# mix.net
KiCad netlist of a schematic drawn in Altium Designer
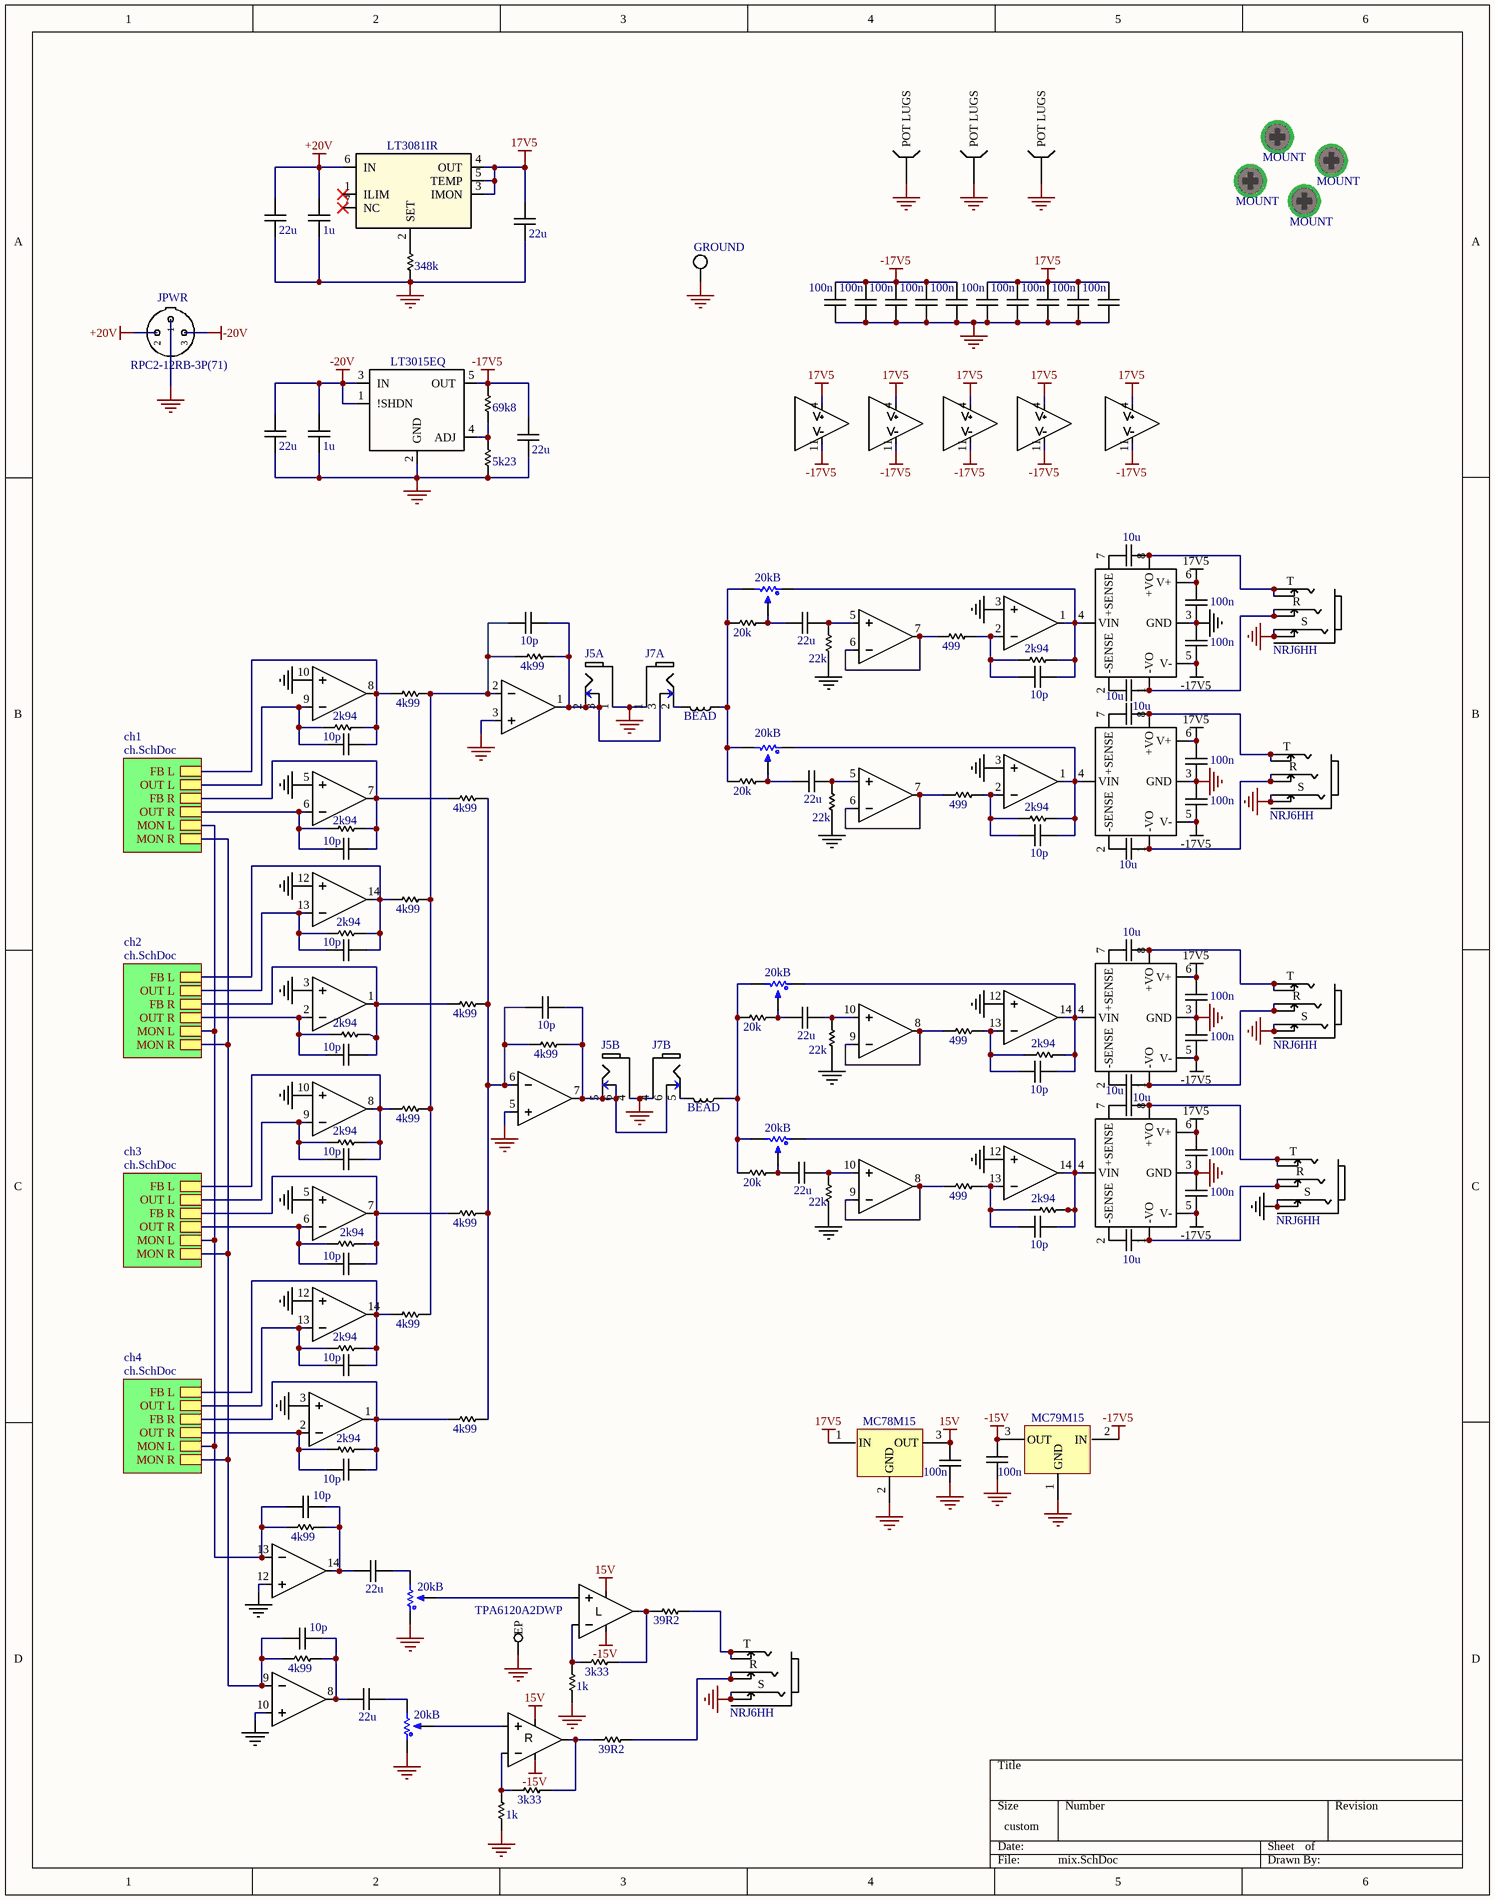
[diagram p0: mix.SchDoc]

(export (version "E")
  (design (tool "Eeschema 10.0.6"))
  (components
    (comp (ref "C5")
      (value "100n")
      (footprint "0805")
      (fields (field (name "PARTNUMBER") "C0805C104K1RAC7800"))
      (libsource (lib "mix") (part "CAP"))
    )
    (comp (ref "C7")
      (value "100n")
      (footprint "0805")
      (fields (field (name "PARTNUMBER") "C0805C104K1RAC7800"))
      (libsource (lib "mix") (part "CAP"))
    )
    (comp (ref "C15")
      (value "100n")
      (footprint "0805")
      (fields (field (name "PARTNUMBER") "C0805C104K1RAC7800"))
      (libsource (lib "mix") (part "CAP"))
    )
    (comp (ref "C17")
      (value "100n")
      (footprint "0805")
      (fields (field (name "PARTNUMBER") "C0805C104K1RAC7800"))
      (libsource (lib "mix") (part "CAP"))
    )
    (comp (ref "C23")
      (value "10p")
      (footprint "0805")
      (fields (field (name "PARTNUMBER") "CC0805JRNPO9BN100"))
      (libsource (lib "mix") (part "CAP"))
    )
    (comp (ref "C24")
      (value "100n")
      (footprint "0805")
      (fields (field (name "PARTNUMBER") "C0805C104K1RAC7800"))
      (libsource (lib "mix") (part "CAP"))
    )
    (comp (ref "C26")
      (value "100n")
      (footprint "0805")
      (fields (field (name "PARTNUMBER") "C0805C104K1RAC7800"))
      (libsource (lib "mix") (part "CAP"))
    )
    (comp (ref "C31")
      (value "100n")
      (footprint "0805")
      (fields (field (name "PARTNUMBER") "C0805C104K1RAC7800"))
      (libsource (lib "mix") (part "CAP"))
    )
    (comp (ref "C33")
      (value "100n")
      (footprint "0805")
      (fields (field (name "PARTNUMBER") "C0805C104K1RAC7800"))
      (libsource (lib "mix") (part "CAP"))
    )
    (comp (ref "C36")
      (value "22u")
      (footprint "0805")
      (fields (field (name "PARTNUMBER") "GRT21BR61E226ME13L"))
      (libsource (lib "mix") (part "CAP"))
    )
    (comp (ref "C37")
      (value "10p")
      (footprint "0805")
      (fields (field (name "PARTNUMBER") "CC0805JRNPO9BN100"))
      (libsource (lib "mix") (part "CAP"))
    )
    (comp (ref "C38")
      (value "100n")
      (footprint "0805")
      (fields (field (name "PARTNUMBER") "C0805C104K1RAC7800"))
      (libsource (lib "mix") (part "CAP"))
    )
    (comp (ref "C39")
      (value "22u")
      (footprint "0805")
      (fields (field (name "PARTNUMBER") "GRT21BR61E226ME13L"))
      (libsource (lib "mix") (part "CAP"))
    )
    (comp (ref "C40")
      (value "100n")
      (footprint "0805")
      (fields (field (name "PARTNUMBER") "C0805C104K1RAC7800"))
      (libsource (lib "mix") (part "CAP"))
    )
    (comp (ref "C41")
      (value "10p")
      (footprint "0805")
      (fields (field (name "PARTNUMBER") "CC0805JRNPO9BN100"))
      (libsource (lib "mix") (part "CAP"))
    )
    (comp (ref "C43")
      (value "10p")
      (footprint "0805")
      (fields (field (name "PARTNUMBER") "CC0805JRNPO9BN100"))
      (libsource (lib "mix") (part "CAP"))
    )
    (comp (ref "C45")
      (value "10p")
      (footprint "0805")
      (fields (field (name "PARTNUMBER") "CC0805JRNPO9BN100"))
      (libsource (lib "mix") (part "CAP"))
    )
    (comp (ref "C46")
      (value "100n")
      (footprint "0805")
      (fields (field (name "PARTNUMBER") "C0805C104K1RAC7800"))
      (libsource (lib "mix") (part "CAP"))
    )
    (comp (ref "C47")
      (value "10p")
      (footprint "0805")
      (fields (field (name "PARTNUMBER") "CC0805JRNPO9BN100"))
      (libsource (lib "mix") (part "CAP"))
    )
    (comp (ref "C48")
      (value "22u")
      (footprint "0805")
      (fields (field (name "PARTNUMBER") "GRT21BR61E226ME13L"))
      (libsource (lib "mix") (part "CAP"))
    )
    (comp (ref "C49")
      (value "100n")
      (footprint "0805")
      (fields (field (name "PARTNUMBER") "C0805C104K1RAC7800"))
      (libsource (lib "mix") (part "CAP"))
    )
    (comp (ref "C50")
      (value "10p")
      (footprint "0805")
      (fields (field (name "PARTNUMBER") "CC0805JRNPO9BN100"))
      (libsource (lib "mix") (part "CAP"))
    )
    (comp (ref "C52")
      (value "22u")
      (footprint "0805")
      (fields (field (name "PARTNUMBER") "GRT21BR61E226ME13L"))
      (libsource (lib "mix") (part "CAP"))
    )
    (comp (ref "C54")
      (value "10p")
      (footprint "0805")
      (fields (field (name "PARTNUMBER") "CC0805JRNPO9BN100"))
      (libsource (lib "mix") (part "CAP"))
    )
    (comp (ref "C55")
      (value "22u")
      (footprint "0805")
      (fields (field (name "PARTNUMBER") "GRT21BR61E226ME13L"))
      (libsource (lib "mix") (part "CAP"))
    )
    (comp (ref "C56")
      (value "10p")
      (footprint "0805")
      (fields (field (name "PARTNUMBER") "CC0805JRNPO9BN100"))
      (libsource (lib "mix") (part "CAP"))
    )
    (comp (ref "C57")
      (value "22u")
      (footprint "0805")
      (fields (field (name "PARTNUMBER") "GRT21BR61E226ME13L"))
      (libsource (lib "mix") (part "CAP"))
    )
    (comp (ref "C58")
      (value "10p")
      (footprint "0805")
      (fields (field (name "PARTNUMBER") "CC0805JRNPO9BN100"))
      (libsource (lib "mix") (part "CAP"))
    )
    (comp (ref "C59")
      (value "10p")
      (footprint "0805")
      (fields (field (name "PARTNUMBER") "CC0805JRNPO9BN100"))
      (libsource (lib "mix") (part "CAP"))
    )
    (comp (ref "C60")
      (value "10p")
      (footprint "0805")
      (fields (field (name "PARTNUMBER") "CC0805JRNPO9BN100"))
      (libsource (lib "mix") (part "CAP"))
    )
    (comp (ref "C61")
      (value "10p")
      (footprint "0805")
      (fields (field (name "PARTNUMBER") "CC0805JRNPO9BN100"))
      (libsource (lib "mix") (part "CAP"))
    )
    (comp (ref "C62")
      (value "10p")
      (footprint "0805")
      (fields (field (name "PARTNUMBER") "CC0805JRNPO9BN100"))
      (libsource (lib "mix") (part "CAP"))
    )
    (comp (ref "C63")
      (value "10p")
      (footprint "0805")
      (fields (field (name "PARTNUMBER") "CC0805JRNPO9BN100"))
      (libsource (lib "mix") (part "CAP"))
    )
    (comp (ref "C64")
      (value "10p")
      (footprint "0805")
      (fields (field (name "PARTNUMBER") "CC0805JRNPO9BN100"))
      (libsource (lib "mix") (part "CAP"))
    )
    (comp (ref "C983")
      (value "22u")
      (footprint "0805")
      (fields (field (name "PARTNUMBER") "GRT21BR61E226ME13L"))
      (libsource (lib "mix") (part "CAP"))
    )
    (comp (ref "C984")
      (value "1u")
      (footprint "0805")
      (fields (field (name "PARTNUMBER") "CL21B105KBFNNNF"))
      (libsource (lib "mix") (part "CAP"))
    )
    (comp (ref "C985")
      (value "22u")
      (footprint "0805")
      (fields (field (name "PARTNUMBER") "GRT21BR61E226ME13L"))
      (libsource (lib "mix") (part "CAP"))
    )
    (comp (ref "C988")
      (value "22u")
      (footprint "0805")
      (fields (field (name "PARTNUMBER") "GRT21BR61E226ME13L"))
      (libsource (lib "mix") (part "CAP"))
    )
    (comp (ref "C989")
      (value "1u")
      (footprint "0805")
      (fields (field (name "PARTNUMBER") "CL21B105KBFNNNF"))
      (libsource (lib "mix") (part "CAP"))
    )
    (comp (ref "C990")
      (value "22u")
      (footprint "0805")
      (fields (field (name "PARTNUMBER") "GRT21BR61E226ME13L"))
      (libsource (lib "mix") (part "CAP"))
    )
    (comp (ref "C1002")
      (value "100n")
      (footprint "0805")
      (fields (field (name "PARTNUMBER") "C0805C104K1RAC7800"))
      (libsource (lib "mix") (part "CAP"))
    )
    (comp (ref "C1003")
      (value "100n")
      (footprint "0805")
      (fields (field (name "PARTNUMBER") "C0805C104K1RAC7800"))
      (libsource (lib "mix") (part "CAP"))
    )
    (comp (ref "C1004")
      (value "100n")
      (footprint "0805")
      (fields (field (name "PARTNUMBER") "C0805C104K1RAC7800"))
      (libsource (lib "mix") (part "CAP"))
    )
    (comp (ref "C1005")
      (value "100n")
      (footprint "0805")
      (fields (field (name "PARTNUMBER") "C0805C104K1RAC7800"))
      (libsource (lib "mix") (part "CAP"))
    )
    (comp (ref "C1006")
      (value "100n")
      (footprint "0805")
      (fields (field (name "PARTNUMBER") "C0805C104K1RAC7800"))
      (libsource (lib "mix") (part "CAP"))
    )
    (comp (ref "C1007")
      (value "100n")
      (footprint "0805")
      (fields (field (name "PARTNUMBER") "C0805C104K1RAC7800"))
      (libsource (lib "mix") (part "CAP"))
    )
    (comp (ref "C1008")
      (value "100n")
      (footprint "0805")
      (fields (field (name "PARTNUMBER") "C0805C104K1RAC7800"))
      (libsource (lib "mix") (part "CAP"))
    )
    (comp (ref "C1010")
      (value "100n")
      (footprint "0805")
      (fields (field (name "PARTNUMBER") "C0805C104K1RAC7800"))
      (libsource (lib "mix") (part "CAP"))
    )
    (comp (ref "C2001")
      (value "10u")
      (footprint "0805")
      (fields (field (name "PARTNUMBER") "NMC0805X5R106K25TRPLP2KF"))
      (libsource (lib "mix") (part "CAP"))
    )
    (comp (ref "C2002")
      (value "10u")
      (footprint "0805")
      (fields (field (name "PARTNUMBER") "NMC0805X5R106K25TRPLP2KF"))
      (libsource (lib "mix") (part "CAP"))
    )
    (comp (ref "C2003")
      (value "10u")
      (footprint "0805")
      (fields (field (name "PARTNUMBER") "NMC0805X5R106K25TRPLP2KF"))
      (libsource (lib "mix") (part "CAP"))
    )
    (comp (ref "C2004")
      (value "10u")
      (footprint "0805")
      (fields (field (name "PARTNUMBER") "NMC0805X5R106K25TRPLP2KF"))
      (libsource (lib "mix") (part "CAP"))
    )
    (comp (ref "C2005")
      (value "10u")
      (footprint "0805")
      (fields (field (name "PARTNUMBER") "NMC0805X5R106K25TRPLP2KF"))
      (libsource (lib "mix") (part "CAP"))
    )
    (comp (ref "C2006")
      (value "10u")
      (footprint "0805")
      (fields (field (name "PARTNUMBER") "NMC0805X5R106K25TRPLP2KF"))
      (libsource (lib "mix") (part "CAP"))
    )
    (comp (ref "C2007")
      (value "10u")
      (footprint "0805")
      (fields (field (name "PARTNUMBER") "NMC0805X5R106K25TRPLP2KF"))
      (libsource (lib "mix") (part "CAP"))
    )
    (comp (ref "C2008")
      (value "10u")
      (footprint "0805")
      (fields (field (name "PARTNUMBER") "NMC0805X5R106K25TRPLP2KF"))
      (libsource (lib "mix") (part "CAP"))
    )
    (comp (ref "GROUND") (value "PHONO") (footprint "PAD") (libsource (lib "mix") (part "PAD")))
    (comp (ref "J1")
      (value "NRJ6HH")
      (footprint "NRJ6HH")
      (fields (field (name "PARTNUMBER") "NRJ6HH-AU"))
      (libsource (lib "mix") (part "NRJ6HH"))
    )
    (comp (ref "J2")
      (value "NRJ6HH")
      (footprint "NRJ6HH")
      (fields (field (name "PARTNUMBER") "NRJ6HH-AU"))
      (libsource (lib "mix") (part "NRJ6HH"))
    )
    (comp (ref "J3")
      (value "NRJ6HH")
      (footprint "NRJ6HH")
      (fields (field (name "PARTNUMBER") "NRJ6HH-AU"))
      (libsource (lib "mix") (part "NRJ6HH"))
    )
    (comp (ref "J4")
      (value "NRJ6HH")
      (footprint "NRJ6HH")
      (fields (field (name "PARTNUMBER") "NRJ6HH-AU"))
      (libsource (lib "mix") (part "NRJ6HH"))
    )
    (comp (ref "J5")
      (value "PJRAN2X1U01AUX")
      (footprint "PJRAN2X1U01AUX")
      (libsource (lib "mix") (part "PJRAN2X1U01AUX"))
    )
    (comp (ref "J6")
      (value "NRJ6HH")
      (footprint "NRJ6HH")
      (fields (field (name "PARTNUMBER") "NRJ6HH-AU"))
      (libsource (lib "mix") (part "NRJ6HH"))
    )
    (comp (ref "J7")
      (value "PJRAN2X1U01AUX")
      (footprint "PJRAN2X1U01AUX")
      (libsource (lib "mix") (part "PJRAN2X1U01AUX"))
    )
    (comp (ref "JPWR")
      (value "RPC2-12RB-3P(71)")
      (footprint "RPC2-12RB-3P(71)")
      (libsource (lib "mix") (part "RPC2-12RB-3P(71)"))
    )
    (comp (ref "L3")
      (value "BEAD")
      (footprint "0805")
      (fields (field (name "PARTNUMBER") "BLM21PG121SH1D"))
      (libsource (lib "mix") (part "BLM21PG121SH1D"))
    )
    (comp (ref "L4")
      (value "BEAD")
      (footprint "0805")
      (fields (field (name "PARTNUMBER") "BLM21PG121SH1D"))
      (libsource (lib "mix") (part "BLM21PG121SH1D"))
    )
    (comp (ref "MH1") (value "MOUNT") (footprint "MOUNT") (libsource (lib "mix") (part "MOUNT")))
    (comp (ref "MH2") (value "MOUNT") (footprint "MOUNT") (libsource (lib "mix") (part "MOUNT")))
    (comp (ref "MH3") (value "MOUNT") (footprint "MOUNT") (libsource (lib "mix") (part "MOUNT")))
    (comp (ref "MH4") (value "MOUNT") (footprint "MOUNT") (libsource (lib "mix") (part "MOUNT")))
    (comp (ref "R5")
      (value "20kB")
      (footprint "P0925N-FC15AR10K")
      (description "P0925N-FC15BR20K")
      (libsource (lib "") (part "P0925N-FC15BR20K_2"))
    )
    (comp (ref "R6")
      (value "20kB")
      (footprint "P0925N-FC15AR10K")
      (description "P0925N-FC15BR20K")
      (libsource (lib "") (part "P0925N-FC15BR20K_2"))
    )
    (comp (ref "R7")
      (value "20kB")
      (footprint "P0925N-FC15AR10K")
      (description "P0925N-FC15BR20K")
      (libsource (lib "") (part "P0925N-FC15BR20K_2"))
    )
    (comp (ref "R13")
      (value "4k99")
      (footprint "0805")
      (fields (field (name "PARTNUMBER") "ERJ-6ENF4991V"))
      (libsource (lib "mix") (part "RES"))
    )
    (comp (ref "R26")
      (value "3k33")
      (footprint "0805")
      (fields (field (name "PARTNUMBER") "ERJ-6ENF1002V"))
      (libsource (lib "mix") (part "RES"))
    )
    (comp (ref "R27")
      (value "3k33")
      (footprint "0805")
      (fields (field (name "PARTNUMBER") "ERJ-6ENF1002V"))
      (libsource (lib "mix") (part "RES"))
    )
    (comp (ref "R29")
      (value "1k")
      (footprint "0805")
      (fields (field (name "PARTNUMBER") "ERJ-6ENF1001V"))
      (libsource (lib "mix") (part "RES"))
    )
    (comp (ref "R30")
      (value "39R2")
      (footprint "0805")
      (fields (field (name "PARTNUMBER") "ERJ-6ENF39R2V"))
      (libsource (lib "mix") (part "RES"))
    )
    (comp (ref "R31")
      (value "39R2")
      (footprint "0805")
      (fields (field (name "PARTNUMBER") "ERJ-6ENF39R2V"))
      (libsource (lib "mix") (part "RES"))
    )
    (comp (ref "R32")
      (value "1k")
      (footprint "0805")
      (fields (field (name "PARTNUMBER") "ERJ-6ENF1001V"))
      (libsource (lib "mix") (part "RES"))
    )
    (comp (ref "R47")
      (value "499")
      (footprint "0805")
      (fields (field (name "PARTNUMBER") "ERJ-6ENF4990V"))
      (libsource (lib "mix") (part "RES"))
    )
    (comp (ref "R49")
      (value "22k")
      (footprint "0805")
      (fields (field (name "PARTNUMBER") "ERJ-6ENF2202V"))
      (libsource (lib "mix") (part "RES"))
    )
    (comp (ref "R50")
      (value "2k94")
      (footprint "0805")
      (fields (field (name "PARTNUMBER") "ERJ-6ENF2941V"))
      (libsource (lib "mix") (part "RES"))
    )
    (comp (ref "R51")
      (value "4k99")
      (footprint "0805")
      (fields (field (name "PARTNUMBER") "ERJ-6ENF4991V"))
      (libsource (lib "mix") (part "RES"))
    )
    (comp (ref "R71")
      (value "20k")
      (footprint "0805")
      (fields (field (name "PARTNUMBER") "ERJ-6ENF2002V"))
      (libsource (lib "mix") (part "RES"))
    )
    (comp (ref "R75")
      (value "20k")
      (footprint "0805")
      (fields (field (name "PARTNUMBER") "ERJ-6ENF2002V"))
      (libsource (lib "mix") (part "RES"))
    )
    (comp (ref "R76")
      (value "499")
      (footprint "0805")
      (fields (field (name "PARTNUMBER") "ERJ-6ENF4990V"))
      (libsource (lib "mix") (part "RES"))
    )
    (comp (ref "R77")
      (value "2k94")
      (footprint "0805")
      (fields (field (name "PARTNUMBER") "ERJ-6ENF2941V"))
      (libsource (lib "mix") (part "RES"))
    )
    (comp (ref "R78")
      (value "22k")
      (footprint "0805")
      (fields (field (name "PARTNUMBER") "ERJ-6ENF2202V"))
      (libsource (lib "mix") (part "RES"))
    )
    (comp (ref "R79")
      (value "2k94")
      (footprint "0805")
      (fields (field (name "PARTNUMBER") "ERJ-6ENF2941V"))
      (libsource (lib "mix") (part "RES"))
    )
    (comp (ref "R80")
      (value "4k99")
      (footprint "0805")
      (fields (field (name "PARTNUMBER") "ERJ-6ENF4991V"))
      (libsource (lib "mix") (part "RES"))
    )
    (comp (ref "R81")
      (value "2k94")
      (footprint "0805")
      (fields (field (name "PARTNUMBER") "ERJ-6ENF2941V"))
      (libsource (lib "mix") (part "RES"))
    )
    (comp (ref "R82")
      (value "4k99")
      (footprint "0805")
      (fields (field (name "PARTNUMBER") "ERJ-6ENF4991V"))
      (libsource (lib "mix") (part "RES"))
    )
    (comp (ref "R83")
      (value "2k94")
      (footprint "0805")
      (fields (field (name "PARTNUMBER") "ERJ-6ENF2941V"))
      (libsource (lib "mix") (part "RES"))
    )
    (comp (ref "R84")
      (value "499")
      (footprint "0805")
      (fields (field (name "PARTNUMBER") "ERJ-6ENF4990V"))
      (libsource (lib "mix") (part "RES"))
    )
    (comp (ref "R85")
      (value "4k99")
      (footprint "0805")
      (fields (field (name "PARTNUMBER") "ERJ-6ENF4991V"))
      (libsource (lib "mix") (part "RES"))
    )
    (comp (ref "R86")
      (value "22k")
      (footprint "0805")
      (fields (field (name "PARTNUMBER") "ERJ-6ENF2202V"))
      (libsource (lib "mix") (part "RES"))
    )
    (comp (ref "R87")
      (value "2k94")
      (footprint "0805")
      (fields (field (name "PARTNUMBER") "ERJ-6ENF2941V"))
      (libsource (lib "mix") (part "RES"))
    )
    (comp (ref "R88")
      (value "4k99")
      (footprint "0805")
      (fields (field (name "PARTNUMBER") "ERJ-6ENF4991V"))
      (libsource (lib "mix") (part "RES"))
    )
    (comp (ref "R89")
      (value "2k94")
      (footprint "0805")
      (fields (field (name "PARTNUMBER") "ERJ-6ENF2941V"))
      (libsource (lib "mix") (part "RES"))
    )
    (comp (ref "R90")
      (value "499")
      (footprint "0805")
      (fields (field (name "PARTNUMBER") "ERJ-6ENF4990V"))
      (libsource (lib "mix") (part "RES"))
    )
    (comp (ref "R91")
      (value "22k")
      (footprint "0805")
      (fields (field (name "PARTNUMBER") "ERJ-6ENF2202V"))
      (libsource (lib "mix") (part "RES"))
    )
    (comp (ref "R92")
      (value "4k99")
      (footprint "0805")
      (fields (field (name "PARTNUMBER") "ERJ-6ENF4991V"))
      (libsource (lib "mix") (part "RES"))
    )
    (comp (ref "R93")
      (value "2k94")
      (footprint "0805")
      (fields (field (name "PARTNUMBER") "ERJ-6ENF2941V"))
      (libsource (lib "mix") (part "RES"))
    )
    (comp (ref "R94")
      (value "2k94")
      (footprint "0805")
      (fields (field (name "PARTNUMBER") "ERJ-6ENF2941V"))
      (libsource (lib "mix") (part "RES"))
    )
    (comp (ref "R95")
      (value "4k99")
      (footprint "0805")
      (fields (field (name "PARTNUMBER") "ERJ-6ENF4991V"))
      (libsource (lib "mix") (part "RES"))
    )
    (comp (ref "R96")
      (value "2k94")
      (footprint "0805")
      (fields (field (name "PARTNUMBER") "ERJ-6ENF2941V"))
      (libsource (lib "mix") (part "RES"))
    )
    (comp (ref "R97")
      (value "4k99")
      (footprint "0805")
      (fields (field (name "PARTNUMBER") "ERJ-6ENF4991V"))
      (libsource (lib "mix") (part "RES"))
    )
    (comp (ref "R98")
      (value "2k94")
      (footprint "0805")
      (fields (field (name "PARTNUMBER") "ERJ-6ENF2941V"))
      (libsource (lib "mix") (part "RES"))
    )
    (comp (ref "R99")
      (value "4k99")
      (footprint "0805")
      (fields (field (name "PARTNUMBER") "ERJ-6ENF4991V"))
      (libsource (lib "mix") (part "RES"))
    )
    (comp (ref "R100")
      (value "2k94")
      (footprint "0805")
      (fields (field (name "PARTNUMBER") "ERJ-6ENF2941V"))
      (libsource (lib "mix") (part "RES"))
    )
    (comp (ref "R101")
      (value "348k")
      (footprint "0805")
      (fields (field (name "PARTNUMBER") "ERJ-PB6B3483V"))
      (libsource (lib "mix") (part "RES"))
    )
    (comp (ref "R102")
      (value "5k23")
      (footprint "0805")
      (fields (field (name "PARTNUMBER") "ERJ-PB6B5231V"))
      (libsource (lib "mix") (part "RES"))
    )
    (comp (ref "R103")
      (value "69k8")
      (footprint "0805")
      (fields (field (name "PARTNUMBER") "ERJ-PB6B6982V"))
      (libsource (lib "mix") (part "RES"))
    )
    (comp (ref "R104")
      (value "20k")
      (footprint "0805")
      (fields (field (name "PARTNUMBER") "ERJ-6ENF2002V"))
      (libsource (lib "mix") (part "RES"))
    )
    (comp (ref "R105")
      (value "20k")
      (footprint "0805")
      (fields (field (name "PARTNUMBER") "ERJ-6ENF2002V"))
      (libsource (lib "mix") (part "RES"))
    )
    (comp (ref "R106")
      (value "4k99")
      (footprint "0805")
      (fields (field (name "PARTNUMBER") "ERJ-6ENF4991V"))
      (libsource (lib "mix") (part "RES"))
    )
    (comp (ref "R107")
      (value "4k99")
      (footprint "0805")
      (fields (field (name "PARTNUMBER") "ERJ-6ENF4991V"))
      (libsource (lib "mix") (part "RES"))
    )
    (comp (ref "U6")
      (value "OPA16X4")
      (footprint "SOIC127P600X175-14M")
      (fields (field (name "PARTNUMBER") "OPA1664AIDR"))
      (libsource (lib "mix") (part "OPA16X4"))
    )
    (comp (ref "U7")
      (value "OPA16X4")
      (footprint "SOIC127P600X175-14M")
      (fields (field (name "PARTNUMBER") "OPA1664AIDR"))
      (libsource (lib "mix") (part "OPA16X4"))
    )
    (comp (ref "U8")
      (value "OPA16X4")
      (footprint "SOIC127P600X175-14M")
      (fields (field (name "PARTNUMBER") "OPA1664AIDR"))
      (libsource (lib "mix") (part "OPA16X4"))
    )
    (comp (ref "U9")
      (value "OPA16X4")
      (footprint "SOIC127P600X175-14M")
      (fields (field (name "PARTNUMBER") "OPA1664AIDR"))
      (libsource (lib "mix") (part "OPA16X4"))
    )
    (comp (ref "U10")
      (value "OPA16X4")
      (footprint "SOIC127P600X175-14M")
      (fields (field (name "PARTNUMBER") "OPA1664AIDR"))
      (libsource (lib "mix") (part "OPA16X4"))
    )
    (comp (ref "U11")
      (value "LT3081IR")
      (footprint "DDPAK-7")
      (description "Imported")
      (fields (field (name "PARTNUMBER") "LT3081IR#PBF"))
      (libsource (lib "mix") (part "LT3081IR"))
    )
    (comp (ref "U12")
      (value "LT3015EQ")
      (footprint "DDPAK-5_Q")
      (fields (field (name "PARTNUMBER") "LT3015EQ#PBF"))
      (libsource (lib "mix") (part "LT3015EQ"))
    )
    (comp (ref "U13")
      (value "DRV135")
      (footprint "SOIC127P600X175-8M")
      (fields (field (name "PARTNUMBER") "DRV135UAG4"))
      (libsource (lib "mix") (part "DRV135UA"))
    )
    (comp (ref "U14")
      (value "DRV135")
      (footprint "SOIC127P600X175-8M")
      (fields (field (name "PARTNUMBER") "DRV135UAG4"))
      (libsource (lib "mix") (part "DRV135UA"))
    )
    (comp (ref "U15")
      (value "DRV135")
      (footprint "SOIC127P600X175-8M")
      (fields (field (name "PARTNUMBER") "DRV135UAG4"))
      (libsource (lib "mix") (part "DRV135UA"))
    )
    (comp (ref "U16")
      (value "DRV135")
      (footprint "SOIC127P600X175-8M")
      (fields (field (name "PARTNUMBER") "DRV135UAG4"))
      (libsource (lib "mix") (part "DRV135UA"))
    )
    (comp (ref "U17")
      (value "TPA6120A2DWP")
      (footprint "SOIC127P1040X265_HS-21M")
      (fields (field (name "PARTNUMBER") "TPA6120A2DWPR"))
      (libsource (lib "mix") (part "TPA6120A2DWP"))
    )
    (comp (ref "U18")
      (value "MC78M15")
      (footprint "DPAK-3")
      (fields (field (name "PARTNUMBER") "MC78M15CDTRKG"))
      (libsource (lib "mix") (part "MC78M15CDTRKG"))
    )
    (comp (ref "U19")
      (value "MC79M15")
      (footprint "DPAK-3")
      (fields (field (name "PARTNUMBER") "MC79M15CDTRKG"))
      (libsource (lib "mix") (part "MC79M15CDTRKG"))
    )
  )
  (nets
    (net (code "1") (name "+20V") (class "Default")
      (node (ref "C983") (pin "2") (pinfunction "2_2") (pintype "passive"))
      (node (ref "C984") (pin "2") (pinfunction "2_2") (pintype "passive"))
      (node (ref "JPWR") (pin "2") (pinfunction "2_2") (pintype "passive"))
      (node (ref "U11") (pin "6") (pinfunction "IN_6") (pintype "passive"))
    )
    (net (code "2") (name "-15V") (class "Default")
      (node (ref "C1003") (pin "1") (pinfunction "1_1") (pintype "passive"))
      (node (ref "U17") (pin "1") (pinfunction "LV-_1") (pintype "passive"))
      (node (ref "U17") (pin "20") (pinfunction "RV-_20") (pintype "passive"))
      (node (ref "U19") (pin "3") (pinfunction "OUT_3") (pintype "passive"))
    )
    (net (code "3") (name "-17V5") (class "Default")
      (node (ref "C1004") (pin "1") (pinfunction "1_1") (pintype "passive"))
      (node (ref "C1006") (pin "1") (pinfunction "1_1") (pintype "passive"))
      (node (ref "C1008") (pin "1") (pinfunction "1_1") (pintype "passive"))
      (node (ref "C26") (pin "2") (pinfunction "2_2") (pintype "passive"))
      (node (ref "C33") (pin "2") (pinfunction "2_2") (pintype "passive"))
      (node (ref "C40") (pin "2") (pinfunction "2_2") (pintype "passive"))
      (node (ref "C49") (pin "2") (pinfunction "2_2") (pintype "passive"))
      (node (ref "C5") (pin "1") (pinfunction "1_1") (pintype "passive"))
      (node (ref "C7") (pin "1") (pinfunction "1_1") (pintype "passive"))
      (node (ref "C990") (pin "2") (pinfunction "2_2") (pintype "passive"))
      (node (ref "R103") (pin "2") (pinfunction "2_2") (pintype "passive"))
      (node (ref "U10") (pin "11") (pinfunction "V-_11") (pintype "passive"))
      (node (ref "U12") (pin "5") (pinfunction "OUT_5") (pintype "passive"))
      (node (ref "U13") (pin "5") (pinfunction "V-_5") (pintype "power_in"))
      (node (ref "U14") (pin "5") (pinfunction "V-_5") (pintype "power_in"))
      (node (ref "U15") (pin "5") (pinfunction "V-_5") (pintype "power_in"))
      (node (ref "U16") (pin "5") (pinfunction "V-_5") (pintype "power_in"))
      (node (ref "U19") (pin "2") (pinfunction "IN_2") (pintype "passive"))
      (node (ref "U6") (pin "11") (pinfunction "V-_11") (pintype "passive"))
      (node (ref "U7") (pin "11") (pinfunction "V-_11") (pintype "passive"))
      (node (ref "U8") (pin "11") (pinfunction "V-_11") (pintype "passive"))
      (node (ref "U9") (pin "11") (pinfunction "V-_11") (pintype "passive"))
    )
    (net (code "4") (name "-20V") (class "Default")
      (node (ref "C988") (pin "2") (pinfunction "2_2") (pintype "passive"))
      (node (ref "C989") (pin "2") (pinfunction "2_2") (pintype "passive"))
      (node (ref "JPWR") (pin "3") (pinfunction "3_3") (pintype "passive"))
      (node (ref "U12") (pin "1") (pinfunction "!SHDN_1") (pintype "passive"))
      (node (ref "U12") (pin "3") (pinfunction "IN_3") (pintype "passive"))
    )
    (net (code "5") (name "/FB L") (class "Default")
      (node (ref "C61") (pin "2") (pinfunction "2_2") (pintype "passive"))
      (node (ref "R97") (pin "1") (pinfunction "1_1") (pintype "passive"))
      (node (ref "R98") (pin "2") (pinfunction "2_2") (pintype "passive"))
      (node (ref "U7") (pin "14") (pinfunction "OUT_D_14") (pintype "passive"))
    )
    (net (code "6") (name "/FB L_1") (class "Default")
      (node (ref "C41") (pin "2") (pinfunction "2_2") (pintype "passive"))
      (node (ref "R51") (pin "1") (pinfunction "1_1") (pintype "passive"))
      (node (ref "R77") (pin "2") (pinfunction "2_2") (pintype "passive"))
      (node (ref "U6") (pin "8") (pinfunction "OUT_C_8") (pintype "passive"))
    )
    (net (code "7") (name "/FB L_2") (class "Default")
      (node (ref "C50") (pin "2") (pinfunction "2_2") (pintype "passive"))
      (node (ref "R82") (pin "1") (pinfunction "1_1") (pintype "passive"))
      (node (ref "R83") (pin "2") (pinfunction "2_2") (pintype "passive"))
      (node (ref "U6") (pin "14") (pinfunction "OUT_D_14") (pintype "passive"))
    )
    (net (code "8") (name "/FB L_3") (class "Default")
      (node (ref "C59") (pin "2") (pinfunction "2_2") (pintype "passive"))
      (node (ref "R92") (pin "1") (pinfunction "1_1") (pintype "passive"))
      (node (ref "R94") (pin "2") (pinfunction "2_2") (pintype "passive"))
      (node (ref "U7") (pin "8") (pinfunction "OUT_C_8") (pintype "passive"))
    )
    (net (code "9") (name "/FB R") (class "Default")
      (node (ref "C62") (pin "2") (pinfunction "2_2") (pintype "passive"))
      (node (ref "R100") (pin "2") (pinfunction "2_2") (pintype "passive"))
      (node (ref "R99") (pin "1") (pinfunction "1_1") (pintype "passive"))
      (node (ref "U7") (pin "1") (pinfunction "OUT_A_1") (pintype "passive"))
    )
    (net (code "10") (name "/FB R_1") (class "Default")
      (node (ref "C45") (pin "2") (pinfunction "2_2") (pintype "passive"))
      (node (ref "R80") (pin "1") (pinfunction "1_1") (pintype "passive"))
      (node (ref "R81") (pin "2") (pinfunction "2_2") (pintype "passive"))
      (node (ref "U6") (pin "7") (pinfunction "OUT_B_7") (pintype "passive"))
    )
    (net (code "11") (name "/FB R_2") (class "Default")
      (node (ref "C56") (pin "2") (pinfunction "2_2") (pintype "passive"))
      (node (ref "R88") (pin "1") (pinfunction "1_1") (pintype "passive"))
      (node (ref "R89") (pin "2") (pinfunction "2_2") (pintype "passive"))
      (node (ref "U6") (pin "1") (pinfunction "OUT_A_1") (pintype "passive"))
    )
    (net (code "12") (name "/FB R_3") (class "Default")
      (node (ref "C60") (pin "2") (pinfunction "2_2") (pintype "passive"))
      (node (ref "R95") (pin "1") (pinfunction "1_1") (pintype "passive"))
      (node (ref "R96") (pin "2") (pinfunction "2_2") (pintype "passive"))
      (node (ref "U7") (pin "7") (pinfunction "OUT_B_7") (pintype "passive"))
    )
    (net (code "13") (name "/MON L") (class "Default")
      (node (ref "C63") (pin "1") (pinfunction "1_1") (pintype "passive"))
      (node (ref "R106") (pin "1") (pinfunction "1_1") (pintype "passive"))
      (node (ref "U10") (pin "13") (pinfunction "IN_D-_13") (pintype "passive"))
    )
    (net (code "14") (name "/MON R") (class "Default")
      (node (ref "C64") (pin "1") (pinfunction "1_1") (pintype "passive"))
      (node (ref "R107") (pin "1") (pinfunction "1_1") (pintype "passive"))
      (node (ref "U10") (pin "9") (pinfunction "IN_C-_9") (pintype "passive"))
    )
    (net (code "15") (name "/OUT L") (class "Default")
      (node (ref "C61") (pin "1") (pinfunction "1_1") (pintype "passive"))
      (node (ref "R98") (pin "1") (pinfunction "1_1") (pintype "passive"))
      (node (ref "U7") (pin "13") (pinfunction "IN_D-_13") (pintype "passive"))
    )
    (net (code "16") (name "/OUT L_1") (class "Default")
      (node (ref "C41") (pin "1") (pinfunction "1_1") (pintype "passive"))
      (node (ref "R77") (pin "1") (pinfunction "1_1") (pintype "passive"))
      (node (ref "U6") (pin "9") (pinfunction "IN_C-_9") (pintype "passive"))
    )
    (net (code "17") (name "/OUT L_2") (class "Default")
      (node (ref "C50") (pin "1") (pinfunction "1_1") (pintype "passive"))
      (node (ref "R83") (pin "1") (pinfunction "1_1") (pintype "passive"))
      (node (ref "U6") (pin "13") (pinfunction "IN_D-_13") (pintype "passive"))
    )
    (net (code "18") (name "/OUT L_3") (class "Default")
      (node (ref "C59") (pin "1") (pinfunction "1_1") (pintype "passive"))
      (node (ref "R94") (pin "1") (pinfunction "1_1") (pintype "passive"))
      (node (ref "U7") (pin "9") (pinfunction "IN_C-_9") (pintype "passive"))
    )
    (net (code "19") (name "/OUT R") (class "Default")
      (node (ref "C60") (pin "1") (pinfunction "1_1") (pintype "passive"))
      (node (ref "R96") (pin "1") (pinfunction "1_1") (pintype "passive"))
      (node (ref "U7") (pin "6") (pinfunction "IN_B-_6") (pintype "passive"))
    )
    (net (code "20") (name "/OUT R_1") (class "Default")
      (node (ref "C45") (pin "1") (pinfunction "1_1") (pintype "passive"))
      (node (ref "R81") (pin "1") (pinfunction "1_1") (pintype "passive"))
      (node (ref "U6") (pin "6") (pinfunction "IN_B-_6") (pintype "passive"))
    )
    (net (code "21") (name "/OUT R_2") (class "Default")
      (node (ref "C56") (pin "1") (pinfunction "1_1") (pintype "passive"))
      (node (ref "R89") (pin "1") (pinfunction "1_1") (pintype "passive"))
      (node (ref "U6") (pin "2") (pinfunction "-IN_A_2") (pintype "passive"))
    )
    (net (code "22") (name "/OUT R_3") (class "Default")
      (node (ref "C62") (pin "1") (pinfunction "1_1") (pintype "passive"))
      (node (ref "R100") (pin "1") (pinfunction "1_1") (pintype "passive"))
      (node (ref "U7") (pin "2") (pinfunction "-IN_A_2") (pintype "passive"))
    )
    (net (code "23") (name "15V") (class "Default")
      (node (ref "C1002") (pin "1") (pinfunction "1_1") (pintype "passive"))
      (node (ref "U17") (pin "18") (pinfunction "RV+_18") (pintype "passive"))
      (node (ref "U17") (pin "3") (pinfunction "LV+_3") (pintype "passive"))
      (node (ref "U18") (pin "3") (pinfunction "OUT_3") (pintype "passive"))
    )
    (net (code "24") (name "17V5") (class "Default")
      (node (ref "C1005") (pin "1") (pinfunction "1_1") (pintype "passive"))
      (node (ref "C1007") (pin "1") (pinfunction "1_1") (pintype "passive"))
      (node (ref "C1010") (pin "1") (pinfunction "1_1") (pintype "passive"))
      (node (ref "C15") (pin "1") (pinfunction "1_1") (pintype "passive"))
      (node (ref "C17") (pin "1") (pinfunction "1_1") (pintype "passive"))
      (node (ref "C24") (pin "1") (pinfunction "1_1") (pintype "passive"))
      (node (ref "C31") (pin "1") (pinfunction "1_1") (pintype "passive"))
      (node (ref "C38") (pin "1") (pinfunction "1_1") (pintype "passive"))
      (node (ref "C46") (pin "1") (pinfunction "1_1") (pintype "passive"))
      (node (ref "C985") (pin "2") (pinfunction "2_2") (pintype "passive"))
      (node (ref "U10") (pin "4") (pinfunction "V+_4") (pintype "passive"))
      (node (ref "U11") (pin "3") (pinfunction "IMON_3") (pintype "passive"))
      (node (ref "U11") (pin "4") (pinfunction "OUT_4") (pintype "passive"))
      (node (ref "U11") (pin "5") (pinfunction "TEMP_5") (pintype "passive"))
      (node (ref "U13") (pin "6") (pinfunction "V+_6") (pintype "power_in"))
      (node (ref "U14") (pin "6") (pinfunction "V+_6") (pintype "power_in"))
      (node (ref "U15") (pin "6") (pinfunction "V+_6") (pintype "power_in"))
      (node (ref "U16") (pin "6") (pinfunction "V+_6") (pintype "power_in"))
      (node (ref "U18") (pin "1") (pinfunction "IN_1") (pintype "passive"))
      (node (ref "U6") (pin "4") (pinfunction "V+_4") (pintype "passive"))
      (node (ref "U7") (pin "4") (pinfunction "V+_4") (pintype "passive"))
      (node (ref "U8") (pin "4") (pinfunction "V+_4") (pintype "passive"))
      (node (ref "U9") (pin "4") (pinfunction "V+_4") (pintype "passive"))
    )
    (net (code "25") (name "GND") (class "Default")
      (node (ref "C1002") (pin "2") (pinfunction "2_2") (pintype "passive"))
      (node (ref "C1003") (pin "2") (pinfunction "2_2") (pintype "passive"))
      (node (ref "C1004") (pin "2") (pinfunction "2_2") (pintype "passive"))
      (node (ref "C1005") (pin "2") (pinfunction "2_2") (pintype "passive"))
      (node (ref "C1006") (pin "2") (pinfunction "2_2") (pintype "passive"))
      (node (ref "C1007") (pin "2") (pinfunction "2_2") (pintype "passive"))
      (node (ref "C1008") (pin "2") (pinfunction "2_2") (pintype "passive"))
      (node (ref "C1010") (pin "2") (pinfunction "2_2") (pintype "passive"))
      (node (ref "C15") (pin "2") (pinfunction "2_2") (pintype "passive"))
      (node (ref "C17") (pin "2") (pinfunction "2_2") (pintype "passive"))
      (node (ref "C24") (pin "2") (pinfunction "2_2") (pintype "passive"))
      (node (ref "C26") (pin "1") (pinfunction "1_1") (pintype "passive"))
      (node (ref "C31") (pin "2") (pinfunction "2_2") (pintype "passive"))
      (node (ref "C33") (pin "1") (pinfunction "1_1") (pintype "passive"))
      (node (ref "C38") (pin "2") (pinfunction "2_2") (pintype "passive"))
      (node (ref "C40") (pin "1") (pinfunction "1_1") (pintype "passive"))
      (node (ref "C46") (pin "2") (pinfunction "2_2") (pintype "passive"))
      (node (ref "C49") (pin "1") (pinfunction "1_1") (pintype "passive"))
      (node (ref "C5") (pin "2") (pinfunction "2_2") (pintype "passive"))
      (node (ref "C7") (pin "2") (pinfunction "2_2") (pintype "passive"))
      (node (ref "C983") (pin "1") (pinfunction "1_1") (pintype "passive"))
      (node (ref "C984") (pin "1") (pinfunction "1_1") (pintype "passive"))
      (node (ref "C985") (pin "1") (pinfunction "1_1") (pintype "passive"))
      (node (ref "C988") (pin "1") (pinfunction "1_1") (pintype "passive"))
      (node (ref "C989") (pin "1") (pinfunction "1_1") (pintype "passive"))
      (node (ref "C990") (pin "1") (pinfunction "1_1") (pintype "passive"))
      (node (ref "GROUND") (pin "1") (pinfunction "1_1") (pintype "passive"))
      (node (ref "J1") (pin "S") (pinfunction "S_S") (pintype "passive"))
      (node (ref "J1") (pin "SN") (pinfunction "SN_SN") (pintype "passive"))
      (node (ref "J2") (pin "S") (pinfunction "S_S") (pintype "passive"))
      (node (ref "J2") (pin "SN") (pinfunction "SN_SN") (pintype "passive"))
      (node (ref "J3") (pin "S") (pinfunction "S_S") (pintype "passive"))
      (node (ref "J3") (pin "SN") (pinfunction "SN_SN") (pintype "passive"))
      (node (ref "J4") (pin "S") (pinfunction "S_S") (pintype "passive"))
      (node (ref "J4") (pin "SN") (pinfunction "SN_SN") (pintype "passive"))
      (node (ref "J5") (pin "1") (pinfunction "1_1") (pintype "passive"))
      (node (ref "J5") (pin "4") (pinfunction "4_4") (pintype "passive"))
      (node (ref "J6") (pin "S") (pinfunction "S_S") (pintype "passive"))
      (node (ref "J6") (pin "SN") (pinfunction "SN_SN") (pintype "passive"))
      (node (ref "J7") (pin "1") (pinfunction "1_1") (pintype "passive"))
      (node (ref "J7") (pin "4") (pinfunction "4_4") (pintype "passive"))
      (node (ref "JPWR") (pin "1") (pinfunction "1_1") (pintype "passive"))
      (node (ref "R101") (pin "1") (pinfunction "1_1") (pintype "passive"))
      (node (ref "R102") (pin "1") (pinfunction "1_1") (pintype "passive"))
      (node (ref "R29") (pin "1") (pinfunction "1_1") (pintype "passive"))
      (node (ref "R32") (pin "1") (pinfunction "1_1") (pintype "passive"))
      (node (ref "R49") (pin "1") (pinfunction "1_1") (pintype "passive"))
      (node (ref "R5") (pin "7") (pinfunction "POT_LUGS_7") (pintype "passive"))
      (node (ref "R6") (pin "7") (pinfunction "POT_LUGS_7") (pintype "passive"))
      (node (ref "R7") (pin "1") (pinfunction "1_1") (pintype "passive"))
      (node (ref "R7") (pin "4") (pinfunction "4_4") (pintype "passive"))
      (node (ref "R7") (pin "7") (pinfunction "POT_LUGS_7") (pintype "passive"))
      (node (ref "R78") (pin "1") (pinfunction "1_1") (pintype "passive"))
      (node (ref "R86") (pin "1") (pinfunction "1_1") (pintype "passive"))
      (node (ref "R91") (pin "1") (pinfunction "1_1") (pintype "passive"))
      (node (ref "U10") (pin "10") (pinfunction "IN_C+_10") (pintype "passive"))
      (node (ref "U10") (pin "12") (pinfunction "IN_D+_12") (pintype "passive"))
      (node (ref "U10") (pin "3") (pinfunction "+IN_A_3") (pintype "passive"))
      (node (ref "U10") (pin "5") (pinfunction "IN_B+_5") (pintype "passive"))
      (node (ref "U12") (pin "2") (pinfunction "GND_2") (pintype "power_in"))
      (node (ref "U13") (pin "3") (pinfunction "GND_3") (pintype "passive"))
      (node (ref "U14") (pin "3") (pinfunction "GND_3") (pintype "passive"))
      (node (ref "U15") (pin "3") (pinfunction "GND_3") (pintype "passive"))
      (node (ref "U16") (pin "3") (pinfunction "GND_3") (pintype "passive"))
      (node (ref "U17") (pin "21") (pinfunction "EP_21") (pintype "passive"))
      (node (ref "U18") (pin "2") (pinfunction "GND_2") (pintype "passive"))
      (node (ref "U19") (pin "1") (pinfunction "GND_1") (pintype "passive"))
      (node (ref "U6") (pin "10") (pinfunction "IN_C+_10") (pintype "passive"))
      (node (ref "U6") (pin "12") (pinfunction "IN_D+_12") (pintype "passive"))
      (node (ref "U6") (pin "3") (pinfunction "+IN_A_3") (pintype "passive"))
      (node (ref "U6") (pin "5") (pinfunction "IN_B+_5") (pintype "passive"))
      (node (ref "U7") (pin "10") (pinfunction "IN_C+_10") (pintype "passive"))
      (node (ref "U7") (pin "12") (pinfunction "IN_D+_12") (pintype "passive"))
      (node (ref "U7") (pin "3") (pinfunction "+IN_A_3") (pintype "passive"))
      (node (ref "U7") (pin "5") (pinfunction "IN_B+_5") (pintype "passive"))
      (node (ref "U8") (pin "12") (pinfunction "IN_D+_12") (pintype "passive"))
      (node (ref "U8") (pin "3") (pinfunction "+IN_A_3") (pintype "passive"))
      (node (ref "U9") (pin "12") (pinfunction "IN_D+_12") (pintype "passive"))
      (node (ref "U9") (pin "3") (pinfunction "+IN_A_3") (pintype "passive"))
    )
    (net (code "26") (name "Net-(C36-Pad1)") (class "Default")
      (node (ref "C36") (pin "1") (pinfunction "1_1") (pintype "passive"))
      (node (ref "R5") (pin "2") (pinfunction "2_2") (pintype "passive"))
      (node (ref "R71") (pin "1") (pinfunction "1_1") (pintype "passive"))
    )
    (net (code "27") (name "Net-(C39-Pad1)") (class "Default")
      (node (ref "C39") (pin "1") (pinfunction "1_1") (pintype "passive"))
      (node (ref "R6") (pin "2") (pinfunction "2_2") (pintype "passive"))
      (node (ref "R75") (pin "1") (pinfunction "1_1") (pintype "passive"))
    )
    (net (code "28") (name "Net-(C48-Pad1)") (class "Default")
      (node (ref "C48") (pin "1") (pinfunction "1_1") (pintype "passive"))
      (node (ref "R104") (pin "1") (pinfunction "1_1") (pintype "passive"))
      (node (ref "R5") (pin "5") (pinfunction "5_5") (pintype "passive"))
    )
    (net (code "29") (name "Net-(C52-Pad2)") (class "Default")
      (node (ref "C52") (pin "2") (pinfunction "2_2") (pintype "passive"))
      (node (ref "R7") (pin "3") (pinfunction "3_3") (pintype "passive"))
    )
    (net (code "30") (name "Net-(C55-Pad2)") (class "Default")
      (node (ref "C55") (pin "2") (pinfunction "2_2") (pintype "passive"))
      (node (ref "R7") (pin "6") (pinfunction "6_6") (pintype "passive"))
    )
    (net (code "31") (name "Net-(C57-Pad1)") (class "Default")
      (node (ref "C57") (pin "1") (pinfunction "1_1") (pintype "passive"))
      (node (ref "R105") (pin "1") (pinfunction "1_1") (pintype "passive"))
      (node (ref "R6") (pin "5") (pinfunction "5_5") (pintype "passive"))
    )
    (net (code "32") (name "Net-(J6-PadR)") (class "Default")
      (node (ref "J6") (pin "R") (pinfunction "R_R") (pintype "passive"))
      (node (ref "J6") (pin "RN") (pinfunction "RN_RN") (pintype "passive"))
      (node (ref "R31") (pin "2") (pinfunction "2_2") (pintype "passive"))
    )
    (net (code "33") (name "Net-(J6-PadT)") (class "Default")
      (node (ref "J6") (pin "T") (pinfunction "T_T") (pintype "passive"))
      (node (ref "J6") (pin "TN") (pinfunction "TN_TN") (pintype "passive"))
      (node (ref "R30") (pin "2") (pinfunction "2_2") (pintype "passive"))
    )
    (net (code "34") (name "Net-(J7-Pad2)") (class "Default")
      (node (ref "J7") (pin "2") (pinfunction "2_2") (pintype "passive"))
      (node (ref "L3") (pin "2") (pinfunction "2_2") (pintype "passive"))
    )
    (net (code "35") (name "Net-(J7-Pad5)") (class "Default")
      (node (ref "J7") (pin "5") (pinfunction "5_5") (pintype "passive"))
      (node (ref "L4") (pin "2") (pinfunction "2_2") (pintype "passive"))
    )
    (net (code "36") (name "Net-(L3-Pad1)") (class "Default")
      (node (ref "L3") (pin "1") (pinfunction "1_1") (pintype "passive"))
      (node (ref "R5") (pin "3") (pinfunction "3_3") (pintype "passive"))
      (node (ref "R6") (pin "3") (pinfunction "3_3") (pintype "passive"))
      (node (ref "R71") (pin "2") (pinfunction "2_2") (pintype "passive"))
      (node (ref "R75") (pin "2") (pinfunction "2_2") (pintype "passive"))
    )
    (net (code "37") (name "Net-(L4-Pad1)") (class "Default")
      (node (ref "L4") (pin "1") (pinfunction "1_1") (pintype "passive"))
      (node (ref "R104") (pin "2") (pinfunction "2_2") (pintype "passive"))
      (node (ref "R105") (pin "2") (pinfunction "2_2") (pintype "passive"))
      (node (ref "R5") (pin "6") (pinfunction "6_6") (pintype "passive"))
      (node (ref "R6") (pin "6") (pinfunction "6_6") (pintype "passive"))
    )
    (net (code "38") (name "Net-(U8A--IN_A)") (class "Default")
      (node (ref "C43") (pin "1") (pinfunction "1_1") (pintype "passive"))
      (node (ref "R76") (pin "2") (pinfunction "2_2") (pintype "passive"))
      (node (ref "R79") (pin "1") (pinfunction "1_1") (pintype "passive"))
      (node (ref "U8") (pin "2") (pinfunction "-IN_A_2") (pintype "passive"))
    )
    (net (code "39") (name "Net-(U8B-IN_B+)") (class "Default")
      (node (ref "C39") (pin "2") (pinfunction "2_2") (pintype "passive"))
      (node (ref "R78") (pin "2") (pinfunction "2_2") (pintype "passive"))
      (node (ref "U8") (pin "5") (pinfunction "IN_B+_5") (pintype "passive"))
    )
    (net (code "40") (name "Net-(U8B-IN_B-)") (class "Default")
      (node (ref "R76") (pin "1") (pinfunction "1_1") (pintype "passive"))
      (node (ref "U8") (pin "6") (pinfunction "IN_B-_6") (pintype "passive"))
      (node (ref "U8") (pin "7") (pinfunction "OUT_B_7") (pintype "passive"))
    )
    (net (code "41") (name "Net-(U8C-IN_C+)") (class "Default")
      (node (ref "C57") (pin "2") (pinfunction "2_2") (pintype "passive"))
      (node (ref "R91") (pin "2") (pinfunction "2_2") (pintype "passive"))
      (node (ref "U8") (pin "10") (pinfunction "IN_C+_10") (pintype "passive"))
    )
    (net (code "42") (name "Net-(U8C-IN_C-)") (class "Default")
      (node (ref "R90") (pin "1") (pinfunction "1_1") (pintype "passive"))
      (node (ref "U8") (pin "8") (pinfunction "OUT_C_8") (pintype "passive"))
      (node (ref "U8") (pin "9") (pinfunction "IN_C-_9") (pintype "passive"))
    )
    (net (code "43") (name "Net-(U8D-IN_D-)") (class "Default")
      (node (ref "C58") (pin "1") (pinfunction "1_1") (pintype "passive"))
      (node (ref "R90") (pin "2") (pinfunction "2_2") (pintype "passive"))
      (node (ref "R93") (pin "1") (pinfunction "1_1") (pintype "passive"))
      (node (ref "U8") (pin "13") (pinfunction "IN_D-_13") (pintype "passive"))
    )
    (net (code "44") (name "Net-(U9A--IN_A)") (class "Default")
      (node (ref "C37") (pin "1") (pinfunction "1_1") (pintype "passive"))
      (node (ref "R47") (pin "2") (pinfunction "2_2") (pintype "passive"))
      (node (ref "R50") (pin "1") (pinfunction "1_1") (pintype "passive"))
      (node (ref "U9") (pin "2") (pinfunction "-IN_A_2") (pintype "passive"))
    )
    (net (code "45") (name "Net-(U9B-IN_B+)") (class "Default")
      (node (ref "C36") (pin "2") (pinfunction "2_2") (pintype "passive"))
      (node (ref "R49") (pin "2") (pinfunction "2_2") (pintype "passive"))
      (node (ref "U9") (pin "5") (pinfunction "IN_B+_5") (pintype "passive"))
    )
    (net (code "46") (name "Net-(U9B-IN_B-)") (class "Default")
      (node (ref "R47") (pin "1") (pinfunction "1_1") (pintype "passive"))
      (node (ref "U9") (pin "6") (pinfunction "IN_B-_6") (pintype "passive"))
      (node (ref "U9") (pin "7") (pinfunction "OUT_B_7") (pintype "passive"))
    )
    (net (code "47") (name "Net-(U9C-IN_C+)") (class "Default")
      (node (ref "C48") (pin "2") (pinfunction "2_2") (pintype "passive"))
      (node (ref "R86") (pin "2") (pinfunction "2_2") (pintype "passive"))
      (node (ref "U9") (pin "10") (pinfunction "IN_C+_10") (pintype "passive"))
    )
    (net (code "48") (name "Net-(U9C-IN_C-)") (class "Default")
      (node (ref "R84") (pin "1") (pinfunction "1_1") (pintype "passive"))
      (node (ref "U9") (pin "8") (pinfunction "OUT_C_8") (pintype "passive"))
      (node (ref "U9") (pin "9") (pinfunction "IN_C-_9") (pintype "passive"))
    )
    (net (code "49") (name "Net-(U9D-IN_D-)") (class "Default")
      (node (ref "C54") (pin "1") (pinfunction "1_1") (pintype "passive"))
      (node (ref "R84") (pin "2") (pinfunction "2_2") (pintype "passive"))
      (node (ref "R87") (pin "1") (pinfunction "1_1") (pintype "passive"))
      (node (ref "U9") (pin "13") (pinfunction "IN_D-_13") (pintype "passive"))
    )
    (net (code "50") (name "Net-(U10A--IN_A)") (class "Default")
      (node (ref "C23") (pin "1") (pinfunction "1_1") (pintype "passive"))
      (node (ref "R13") (pin "1") (pinfunction "1_1") (pintype "passive"))
      (node (ref "R51") (pin "2") (pinfunction "2_2") (pintype "passive"))
      (node (ref "R82") (pin "2") (pinfunction "2_2") (pintype "passive"))
      (node (ref "R92") (pin "2") (pinfunction "2_2") (pintype "passive"))
      (node (ref "R97") (pin "2") (pinfunction "2_2") (pintype "passive"))
      (node (ref "U10") (pin "2") (pinfunction "-IN_A_2") (pintype "passive"))
    )
    (net (code "51") (name "Net-(U10A-OUT_A)") (class "Default")
      (node (ref "C23") (pin "2") (pinfunction "2_2") (pintype "passive"))
      (node (ref "J5") (pin "2") (pinfunction "2_2") (pintype "passive"))
      (node (ref "J5") (pin "3") (pinfunction "3_3") (pintype "passive"))
      (node (ref "J7") (pin "3") (pinfunction "3_3") (pintype "passive"))
      (node (ref "R13") (pin "2") (pinfunction "2_2") (pintype "passive"))
      (node (ref "U10") (pin "1") (pinfunction "OUT_A_1") (pintype "passive"))
    )
    (net (code "52") (name "Net-(U10B-IN_B-)") (class "Default")
      (node (ref "C47") (pin "1") (pinfunction "1_1") (pintype "passive"))
      (node (ref "R80") (pin "2") (pinfunction "2_2") (pintype "passive"))
      (node (ref "R85") (pin "1") (pinfunction "1_1") (pintype "passive"))
      (node (ref "R88") (pin "2") (pinfunction "2_2") (pintype "passive"))
      (node (ref "R95") (pin "2") (pinfunction "2_2") (pintype "passive"))
      (node (ref "R99") (pin "2") (pinfunction "2_2") (pintype "passive"))
      (node (ref "U10") (pin "6") (pinfunction "IN_B-_6") (pintype "passive"))
    )
    (net (code "53") (name "Net-(U10B-OUT_B)") (class "Default")
      (node (ref "C47") (pin "2") (pinfunction "2_2") (pintype "passive"))
      (node (ref "J5") (pin "5") (pinfunction "5_5") (pintype "passive"))
      (node (ref "J5") (pin "6") (pinfunction "6_6") (pintype "passive"))
      (node (ref "J7") (pin "6") (pinfunction "6_6") (pintype "passive"))
      (node (ref "R85") (pin "2") (pinfunction "2_2") (pintype "passive"))
      (node (ref "U10") (pin "7") (pinfunction "OUT_B_7") (pintype "passive"))
    )
    (net (code "54") (name "Net-(U10C-OUT_C)") (class "Default")
      (node (ref "C55") (pin "1") (pinfunction "1_1") (pintype "passive"))
      (node (ref "C64") (pin "2") (pinfunction "2_2") (pintype "passive"))
      (node (ref "R107") (pin "2") (pinfunction "2_2") (pintype "passive"))
      (node (ref "U10") (pin "8") (pinfunction "OUT_C_8") (pintype "passive"))
    )
    (net (code "55") (name "Net-(U10D-OUT_D)") (class "Default")
      (node (ref "C52") (pin "1") (pinfunction "1_1") (pintype "passive"))
      (node (ref "C63") (pin "2") (pinfunction "2_2") (pintype "passive"))
      (node (ref "R106") (pin "2") (pinfunction "2_2") (pintype "passive"))
      (node (ref "U10") (pin "14") (pinfunction "OUT_D_14") (pintype "passive"))
    )
    (net (code "56") (name "Net-(U11-SET)") (class "Default")
      (node (ref "R101") (pin "2") (pinfunction "2_2") (pintype "passive"))
      (node (ref "U11") (pin "2") (pinfunction "SET_2") (pintype "passive"))
    )
    (net (code "57") (name "Net-(U12-ADJ)") (class "Default")
      (node (ref "R102") (pin "2") (pinfunction "2_2") (pintype "passive"))
      (node (ref "R103") (pin "1") (pinfunction "1_1") (pintype "passive"))
      (node (ref "U12") (pin "4") (pinfunction "ADJ_4") (pintype "passive"))
    )
    (net (code "58") (name "Net-(U13-+SENSE)") (class "Default")
      (node (ref "C2001") (pin "1") (pinfunction "1_1") (pintype "passive"))
      (node (ref "U13") (pin "7") (pinfunction "+SENSE_7") (pintype "passive"))
    )
    (net (code "59") (name "Net-(U13-+VO)") (class "Default")
      (node (ref "C2001") (pin "2") (pinfunction "2_2") (pintype "passive"))
      (node (ref "J1") (pin "T") (pinfunction "T_T") (pintype "passive"))
      (node (ref "J1") (pin "TN") (pinfunction "TN_TN") (pintype "passive"))
      (node (ref "U13") (pin "8") (pinfunction "+VO_8") (pintype "passive"))
    )
    (net (code "60") (name "Net-(U13--SENSE)") (class "Default")
      (node (ref "C2002") (pin "1") (pinfunction "1_1") (pintype "passive"))
      (node (ref "U13") (pin "2") (pinfunction "-SENSE_2") (pintype "passive"))
    )
    (net (code "61") (name "Net-(U13--VO)") (class "Default")
      (node (ref "C2002") (pin "2") (pinfunction "2_2") (pintype "passive"))
      (node (ref "J1") (pin "R") (pinfunction "R_R") (pintype "passive"))
      (node (ref "J1") (pin "RN") (pinfunction "RN_RN") (pintype "passive"))
      (node (ref "U13") (pin "1") (pinfunction "-VO_1") (pintype "passive"))
    )
    (net (code "62") (name "Net-(U13-VIN)") (class "Default")
      (node (ref "C37") (pin "2") (pinfunction "2_2") (pintype "passive"))
      (node (ref "R5") (pin "1") (pinfunction "1_1") (pintype "passive"))
      (node (ref "R50") (pin "2") (pinfunction "2_2") (pintype "passive"))
      (node (ref "U13") (pin "4") (pinfunction "VIN_4") (pintype "passive"))
      (node (ref "U9") (pin "1") (pinfunction "OUT_A_1") (pintype "passive"))
    )
    (net (code "63") (name "Net-(U14-+SENSE)") (class "Default")
      (node (ref "C2003") (pin "1") (pinfunction "1_1") (pintype "passive"))
      (node (ref "U14") (pin "7") (pinfunction "+SENSE_7") (pintype "passive"))
    )
    (net (code "64") (name "Net-(U14-+VO)") (class "Default")
      (node (ref "C2003") (pin "2") (pinfunction "2_2") (pintype "passive"))
      (node (ref "J2") (pin "T") (pinfunction "T_T") (pintype "passive"))
      (node (ref "J2") (pin "TN") (pinfunction "TN_TN") (pintype "passive"))
      (node (ref "U14") (pin "8") (pinfunction "+VO_8") (pintype "passive"))
    )
    (net (code "65") (name "Net-(U14--SENSE)") (class "Default")
      (node (ref "C2004") (pin "1") (pinfunction "1_1") (pintype "passive"))
      (node (ref "U14") (pin "2") (pinfunction "-SENSE_2") (pintype "passive"))
    )
    (net (code "66") (name "Net-(U14--VO)") (class "Default")
      (node (ref "C2004") (pin "2") (pinfunction "2_2") (pintype "passive"))
      (node (ref "J2") (pin "R") (pinfunction "R_R") (pintype "passive"))
      (node (ref "J2") (pin "RN") (pinfunction "RN_RN") (pintype "passive"))
      (node (ref "U14") (pin "1") (pinfunction "-VO_1") (pintype "passive"))
    )
    (net (code "67") (name "Net-(U14-VIN)") (class "Default")
      (node (ref "C43") (pin "2") (pinfunction "2_2") (pintype "passive"))
      (node (ref "R6") (pin "1") (pinfunction "1_1") (pintype "passive"))
      (node (ref "R79") (pin "2") (pinfunction "2_2") (pintype "passive"))
      (node (ref "U14") (pin "4") (pinfunction "VIN_4") (pintype "passive"))
      (node (ref "U8") (pin "1") (pinfunction "OUT_A_1") (pintype "passive"))
    )
    (net (code "68") (name "Net-(U15-+SENSE)") (class "Default")
      (node (ref "C2005") (pin "1") (pinfunction "1_1") (pintype "passive"))
      (node (ref "U15") (pin "7") (pinfunction "+SENSE_7") (pintype "passive"))
    )
    (net (code "69") (name "Net-(U15-+VO)") (class "Default")
      (node (ref "C2005") (pin "2") (pinfunction "2_2") (pintype "passive"))
      (node (ref "J3") (pin "T") (pinfunction "T_T") (pintype "passive"))
      (node (ref "J3") (pin "TN") (pinfunction "TN_TN") (pintype "passive"))
      (node (ref "U15") (pin "8") (pinfunction "+VO_8") (pintype "passive"))
    )
    (net (code "70") (name "Net-(U15--SENSE)") (class "Default")
      (node (ref "C2006") (pin "1") (pinfunction "1_1") (pintype "passive"))
      (node (ref "U15") (pin "2") (pinfunction "-SENSE_2") (pintype "passive"))
    )
    (net (code "71") (name "Net-(U15--VO)") (class "Default")
      (node (ref "C2006") (pin "2") (pinfunction "2_2") (pintype "passive"))
      (node (ref "J3") (pin "R") (pinfunction "R_R") (pintype "passive"))
      (node (ref "J3") (pin "RN") (pinfunction "RN_RN") (pintype "passive"))
      (node (ref "U15") (pin "1") (pinfunction "-VO_1") (pintype "passive"))
    )
    (net (code "72") (name "Net-(U15-VIN)") (class "Default")
      (node (ref "C54") (pin "2") (pinfunction "2_2") (pintype "passive"))
      (node (ref "R5") (pin "4") (pinfunction "4_4") (pintype "passive"))
      (node (ref "R87") (pin "2") (pinfunction "2_2") (pintype "passive"))
      (node (ref "U15") (pin "4") (pinfunction "VIN_4") (pintype "passive"))
      (node (ref "U9") (pin "14") (pinfunction "OUT_D_14") (pintype "passive"))
    )
    (net (code "73") (name "Net-(U16-+SENSE)") (class "Default")
      (node (ref "C2007") (pin "1") (pinfunction "1_1") (pintype "passive"))
      (node (ref "U16") (pin "7") (pinfunction "+SENSE_7") (pintype "passive"))
    )
    (net (code "74") (name "Net-(U16-+VO)") (class "Default")
      (node (ref "C2007") (pin "2") (pinfunction "2_2") (pintype "passive"))
      (node (ref "J4") (pin "T") (pinfunction "T_T") (pintype "passive"))
      (node (ref "J4") (pin "TN") (pinfunction "TN_TN") (pintype "passive"))
      (node (ref "U16") (pin "8") (pinfunction "+VO_8") (pintype "passive"))
    )
    (net (code "75") (name "Net-(U16--SENSE)") (class "Default")
      (node (ref "C2008") (pin "1") (pinfunction "1_1") (pintype "passive"))
      (node (ref "U16") (pin "2") (pinfunction "-SENSE_2") (pintype "passive"))
    )
    (net (code "76") (name "Net-(U16--VO)") (class "Default")
      (node (ref "C2008") (pin "2") (pinfunction "2_2") (pintype "passive"))
      (node (ref "J4") (pin "R") (pinfunction "R_R") (pintype "passive"))
      (node (ref "J4") (pin "RN") (pinfunction "RN_RN") (pintype "passive"))
      (node (ref "U16") (pin "1") (pinfunction "-VO_1") (pintype "passive"))
    )
    (net (code "77") (name "Net-(U16-VIN)") (class "Default")
      (node (ref "C58") (pin "2") (pinfunction "2_2") (pintype "passive"))
      (node (ref "R6") (pin "4") (pinfunction "4_4") (pintype "passive"))
      (node (ref "R93") (pin "2") (pinfunction "2_2") (pintype "passive"))
      (node (ref "U16") (pin "4") (pinfunction "VIN_4") (pintype "passive"))
      (node (ref "U8") (pin "14") (pinfunction "OUT_D_14") (pintype "passive"))
    )
    (net (code "78") (name "Net-(U17A-LIN+)") (class "Default")
      (node (ref "R7") (pin "2") (pinfunction "2_2") (pintype "passive"))
      (node (ref "U17") (pin "4") (pinfunction "LIN+_4") (pintype "passive"))
    )
    (net (code "79") (name "Net-(U17A-LIN-)") (class "Default")
      (node (ref "R27") (pin "1") (pinfunction "1_1") (pintype "passive"))
      (node (ref "R29") (pin "2") (pinfunction "2_2") (pintype "passive"))
      (node (ref "U17") (pin "5") (pinfunction "LIN-_5") (pintype "passive"))
    )
    (net (code "80") (name "Net-(U17A-LOUT)") (class "Default")
      (node (ref "R27") (pin "2") (pinfunction "2_2") (pintype "passive"))
      (node (ref "R30") (pin "1") (pinfunction "1_1") (pintype "passive"))
      (node (ref "U17") (pin "2") (pinfunction "LOUT_2") (pintype "passive"))
    )
    (net (code "81") (name "Net-(U17B-RIN+)") (class "Default")
      (node (ref "R7") (pin "5") (pinfunction "5_5") (pintype "passive"))
      (node (ref "U17") (pin "17") (pinfunction "RIN+_17") (pintype "passive"))
    )
    (net (code "82") (name "Net-(U17B-RIN-)") (class "Default")
      (node (ref "R26") (pin "1") (pinfunction "1_1") (pintype "passive"))
      (node (ref "R32") (pin "2") (pinfunction "2_2") (pintype "passive"))
      (node (ref "U17") (pin "16") (pinfunction "RIN-_16") (pintype "passive"))
    )
    (net (code "83") (name "Net-(U17B-ROUT)") (class "Default")
      (node (ref "R26") (pin "2") (pinfunction "2_2") (pintype "passive"))
      (node (ref "R31") (pin "1") (pinfunction "1_1") (pintype "passive"))
      (node (ref "U17") (pin "19") (pinfunction "ROUT_19") (pintype "passive"))
    )
    (net (code "84") (name "unconnected-(U11-ILIM-Pad1)") (class "Default")
      (node (ref "U11") (pin "1") (pinfunction "ILIM_1") (pintype "passive+no_connect"))
    )
    (net (code "85") (name "unconnected-(U11-NC-Pad7)") (class "Default")
      (node (ref "U11") (pin "7") (pinfunction "NC_7") (pintype "passive+no_connect"))
    )
  )
)
